# wifi_board.net
KiCad netlist of a schematic drawn in EAGLE
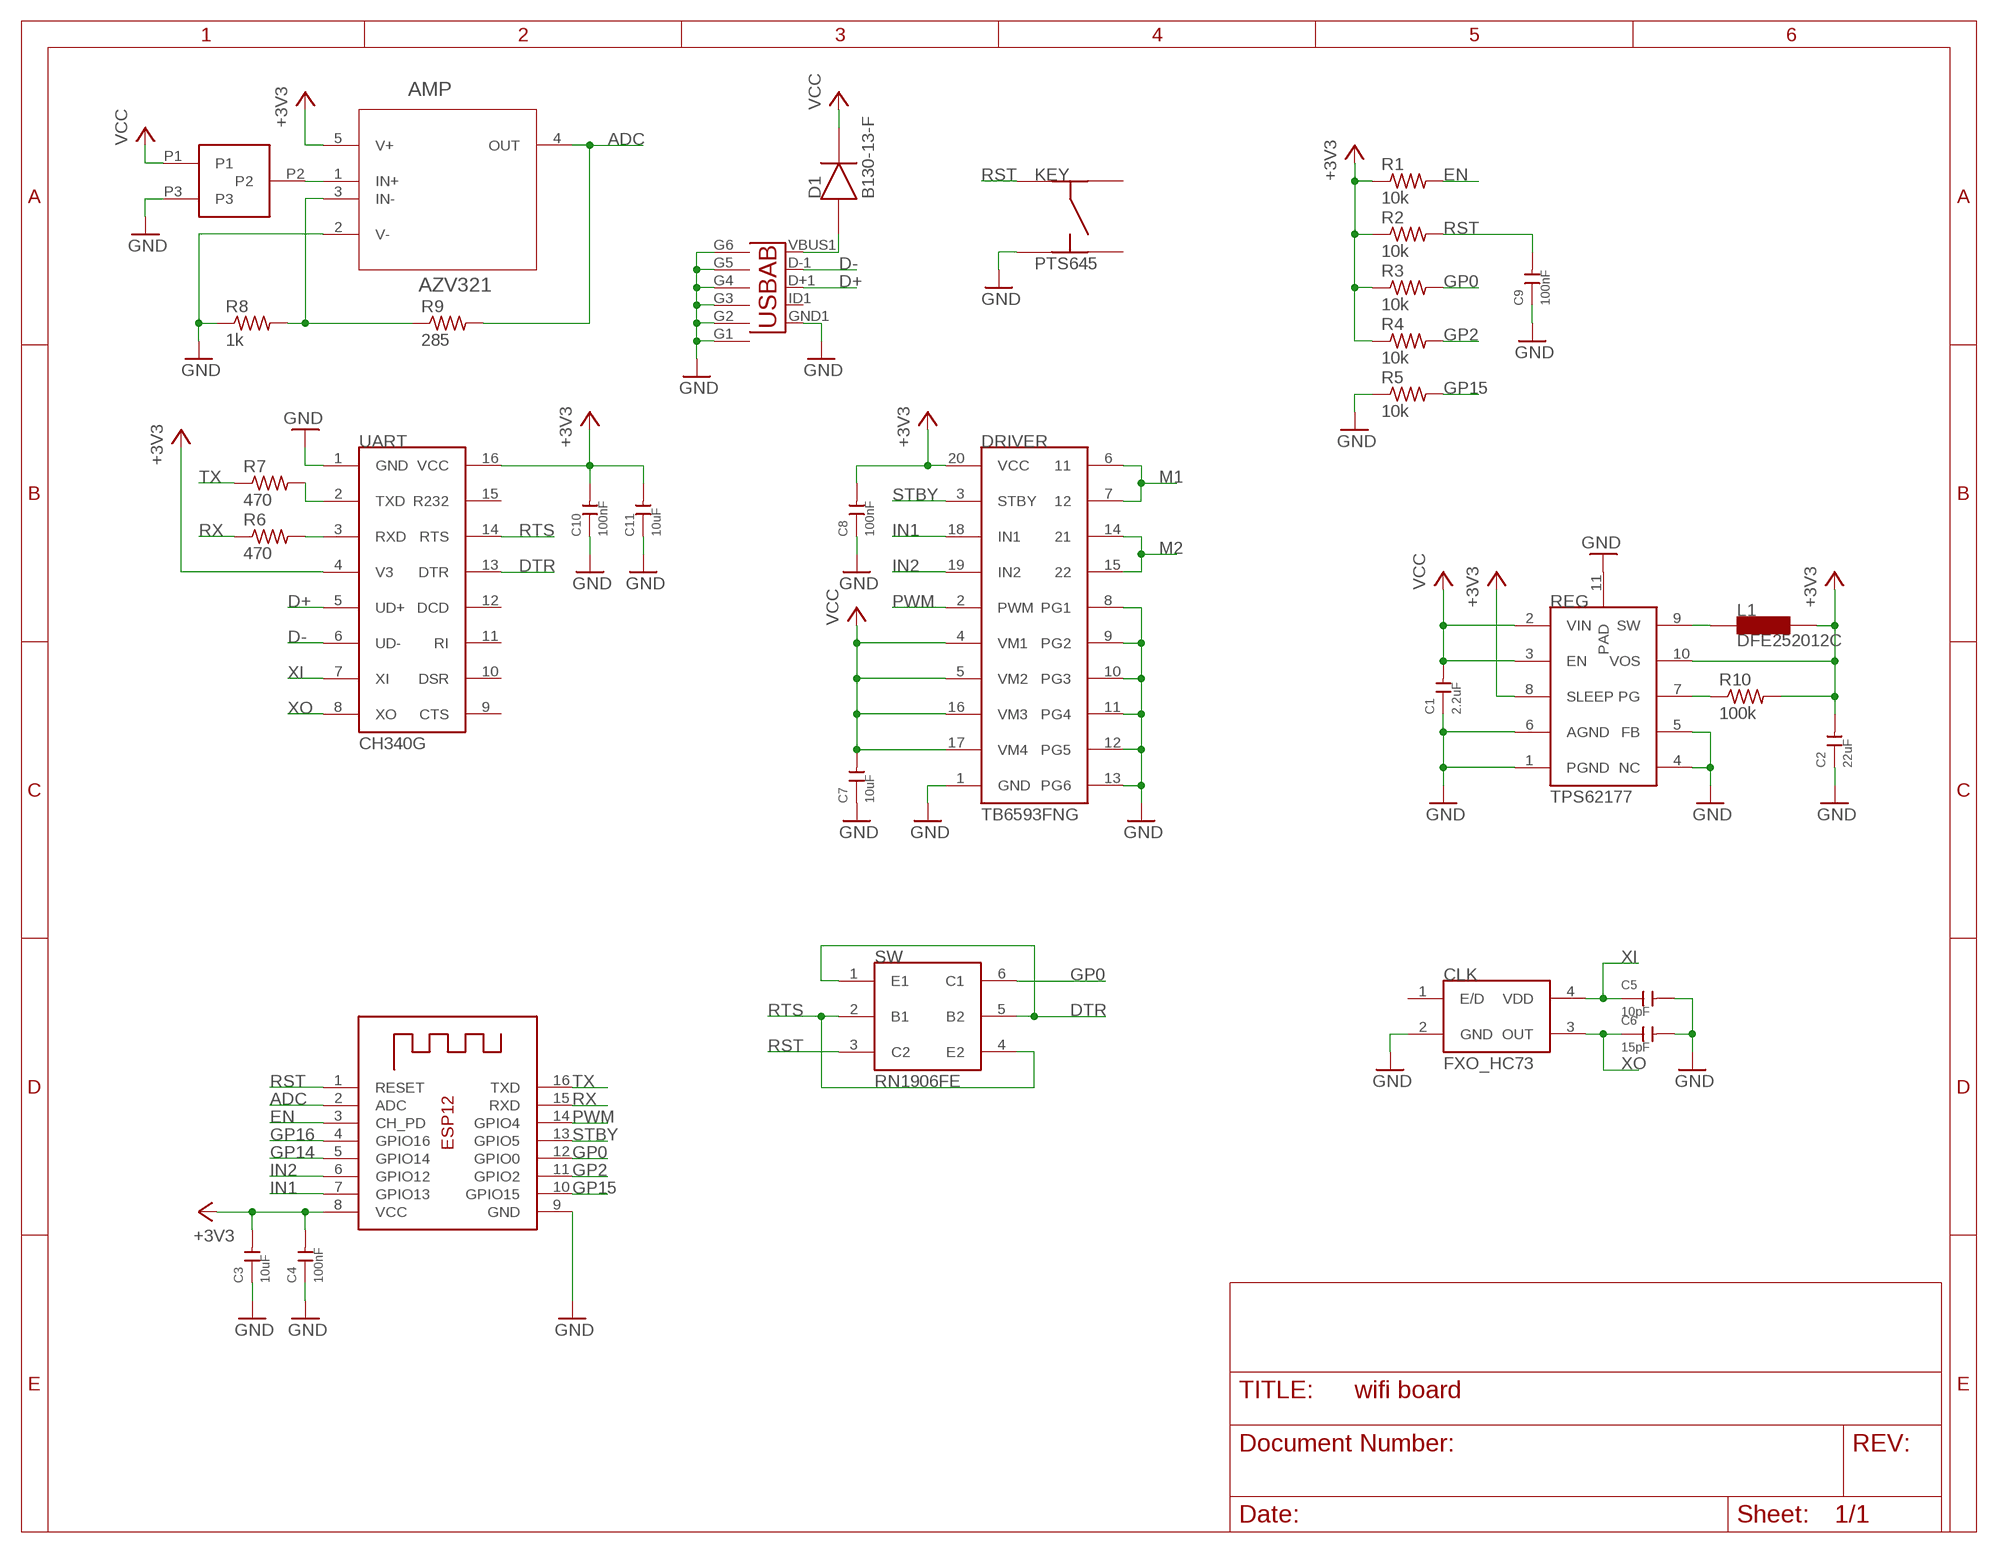
[diagram p0: schematic, sheet 1]

(export (version "E")
  (design (tool "Eeschema 10.0.6"))
  (components
    (comp (ref "AMP")
      (value "AZV321")
      (footprint "eagle-import:SOT65P210X110-5N")
      (fields (field (name "MPN") "LMV321SEG-7"))
      (libsource (lib "eagle-import") (part "LMV321SEG-7"))
    )
    (comp (ref "C1")
      (value "2.2uF")
      (footprint "eagle-import:C0603")
      (libsource (lib "eagle-import") (part "CERAMIC-0.5PF-50V-0.1PF-NPO(0603)"))
    )
    (comp (ref "C2")
      (value "22uF")
      (footprint "eagle-import:C0603")
      (libsource (lib "eagle-import") (part "CERAMIC-0.5PF-50V-0.1PF-NPO(0603)"))
    )
    (comp (ref "C3")
      (value "10uF")
      (footprint "eagle-import:C0603")
      (libsource (lib "eagle-import") (part "CERAMIC-0.5PF-50V-0.1PF-NPO(0603)"))
    )
    (comp (ref "C4")
      (value "100nF")
      (footprint "eagle-import:C0603")
      (libsource (lib "eagle-import") (part "CERAMIC-0.5PF-50V-0.1PF-NPO(0603)"))
    )
    (comp (ref "C5")
      (value "10pF")
      (footprint "eagle-import:C0603")
      (libsource (lib "eagle-import") (part "CERAMIC-0.5PF-50V-0.1PF-NPO(0603)"))
    )
    (comp (ref "C6")
      (value "15pF")
      (footprint "eagle-import:C0603")
      (libsource (lib "eagle-import") (part "CERAMIC-0.5PF-50V-0.1PF-NPO(0603)"))
    )
    (comp (ref "C7")
      (value "10uF")
      (footprint "eagle-import:C0603")
      (libsource (lib "eagle-import") (part "CERAMIC-0.5PF-50V-0.1PF-NPO(0603)"))
    )
    (comp (ref "C8")
      (value "100nF")
      (footprint "eagle-import:C0603")
      (libsource (lib "eagle-import") (part "CERAMIC-0.5PF-50V-0.1PF-NPO(0603)"))
    )
    (comp (ref "C9")
      (value "100nF")
      (footprint "eagle-import:C0603")
      (libsource (lib "eagle-import") (part "CERAMIC-1PF-50V-0.25PF-NPO(0603)"))
    )
    (comp (ref "C10")
      (value "100nF")
      (footprint "eagle-import:C0603")
      (libsource (lib "eagle-import") (part "CERAMIC-0.5PF-50V-0.1PF-NPO(0603)"))
    )
    (comp (ref "C11")
      (value "10uF")
      (footprint "eagle-import:C0603")
      (libsource (lib "eagle-import") (part "CERAMIC-0.5PF-50V-0.1PF-NPO(0603)"))
    )
    (comp (ref "CLK")
      (value "FXO_HC73")
      (footprint "eagle-import:4-SMD")
      (libsource (lib "eagle-import") (part "FXO_HC73"))
    )
    (comp (ref "CONN")
      (value "AVX_CONN")
      (footprint "eagle-import:AVX_CONN")
      (libsource (lib "eagle-import") (part "AVX_CONN"))
    )
    (comp (ref "D1")
      (value "B130-13-F")
      (footprint "eagle-import:SMA")
      (libsource (lib "eagle-import") (part "B130-13-F"))
    )
    (comp (ref "DRIVER")
      (value "TB6593FNG")
      (footprint "eagle-import:SSOP-20")
      (libsource (lib "eagle-import") (part "TB6593FNG"))
    )
    (comp (ref "ESP12")
      (value "ESP-12")
      (footprint "eagle-import:ESP-12")
      (libsource (lib "eagle-import") (part "ESP-12"))
    )
    (comp (ref "KEY")
      (value "PTS645")
      (footprint "eagle-import:BUTTON")
      (libsource (lib "eagle-import") (part "BUTTON"))
    )
    (comp (ref "L1")
      (value "DFE252012C")
      (footprint "eagle-import:1008")
      (libsource (lib "eagle-import") (part "DFE252012C"))
    )
    (comp (ref "R1")
      (value "10k")
      (footprint "eagle-import:R0603")
      (libsource (lib "eagle-import") (part "R-US_R0603"))
    )
    (comp (ref "R2")
      (value "10k")
      (footprint "eagle-import:R0603")
      (libsource (lib "eagle-import") (part "R-US_R0603"))
    )
    (comp (ref "R3")
      (value "10k")
      (footprint "eagle-import:R0603")
      (libsource (lib "eagle-import") (part "R-US_R0603"))
    )
    (comp (ref "R4")
      (value "10k")
      (footprint "eagle-import:R0603")
      (libsource (lib "eagle-import") (part "R-US_R0603"))
    )
    (comp (ref "R5")
      (value "10k")
      (footprint "eagle-import:R0603")
      (libsource (lib "eagle-import") (part "R-US_R0603"))
    )
    (comp (ref "R6")
      (value "470")
      (footprint "eagle-import:R0603")
      (libsource (lib "eagle-import") (part "R-US_R0603"))
    )
    (comp (ref "R7")
      (value "470")
      (footprint "eagle-import:R0603")
      (libsource (lib "eagle-import") (part "R-US_R0603"))
    )
    (comp (ref "R8")
      (value "1k")
      (footprint "eagle-import:R0603")
      (libsource (lib "eagle-import") (part "R-US_R0603"))
    )
    (comp (ref "R9")
      (value "285")
      (footprint "eagle-import:R0603")
      (libsource (lib "eagle-import") (part "R-US_R0603"))
    )
    (comp (ref "R10")
      (value "100k")
      (footprint "eagle-import:R0603")
      (libsource (lib "eagle-import") (part "R-US_R0603"))
    )
    (comp (ref "REG")
      (value "TPS62177")
      (footprint "eagle-import:WSON-10")
      (libsource (lib "eagle-import") (part "TPS62177"))
    )
    (comp (ref "SW")
      (value "RN1906FE")
      (footprint "eagle-import:SOT-563")
      (libsource (lib "eagle-import") (part "RN1906FE"))
    )
    (comp (ref "UART")
      (value "CH340G")
      (footprint "eagle-import:20-16")
      (libsource (lib "eagle-import") (part "CH340G"))
    )
    (comp (ref "USB")
      (value "USB\"\"")
      (footprint "eagle-import:USB-MICRO-SMD")
      (libsource (lib "eagle-import") (part "USB{dblquote}{dblquote}"))
    )
  )
  (nets
    (net (code "1") (name "+3V3") (class "Default")
      (node (ref "AMP") (pin "5") (pinfunction "V+_5") (pintype "power_in"))
      (node (ref "C10") (pin "2") (pinfunction "2_2") (pintype "passive"))
      (node (ref "C11") (pin "2") (pinfunction "2_2") (pintype "passive"))
      (node (ref "C2") (pin "2") (pinfunction "2_2") (pintype "passive"))
      (node (ref "C3") (pin "2") (pinfunction "2_2") (pintype "passive"))
      (node (ref "C4") (pin "2") (pinfunction "2_2") (pintype "passive"))
      (node (ref "C8") (pin "2") (pinfunction "2_2") (pintype "passive"))
      (node (ref "DRIVER") (pin "20") (pinfunction "VCC_20") (pintype "bidirectional"))
      (node (ref "ESP12") (pin "8") (pinfunction "VCC_8") (pintype "power_in"))
      (node (ref "L1") (pin "P$3") (pinfunction "P$2_P$3") (pintype "bidirectional"))
      (node (ref "R1") (pin "1") (pinfunction "1_1") (pintype "passive"))
      (node (ref "R10") (pin "2") (pinfunction "2_2") (pintype "passive"))
      (node (ref "R2") (pin "1") (pinfunction "1_1") (pintype "passive"))
      (node (ref "R3") (pin "1") (pinfunction "1_1") (pintype "passive"))
      (node (ref "R4") (pin "1") (pinfunction "1_1") (pintype "passive"))
      (node (ref "REG") (pin "10") (pinfunction "VOS_10") (pintype "bidirectional"))
      (node (ref "REG") (pin "8") (pinfunction "SLEEP_8") (pintype "bidirectional"))
      (node (ref "UART") (pin "16") (pinfunction "VCC_16") (pintype "bidirectional"))
      (node (ref "UART") (pin "4") (pinfunction "V3_4") (pintype "bidirectional"))
    )
    (net (code "2") (name "/ADC") (class "Default")
      (node (ref "AMP") (pin "4") (pinfunction "OUT_4") (pintype "output"))
      (node (ref "ESP12") (pin "2") (pinfunction "ADC_2") (pintype "passive"))
      (node (ref "R9") (pin "2") (pinfunction "2_2") (pintype "passive"))
    )
    (net (code "3") (name "/D+") (class "Default")
      (node (ref "UART") (pin "5") (pinfunction "UD+_5") (pintype "bidirectional"))
      (node (ref "USB") (pin "D+1") (pinfunction "D+_D+1") (pintype "bidirectional"))
    )
    (net (code "4") (name "/D-") (class "Default")
      (node (ref "UART") (pin "6") (pinfunction "UD-_6") (pintype "bidirectional"))
      (node (ref "USB") (pin "D-1") (pinfunction "D-_D-1") (pintype "bidirectional"))
    )
    (net (code "5") (name "/DTR") (class "Default")
      (node (ref "SW") (pin "1") (pinfunction "E1_1") (pintype "bidirectional"))
      (node (ref "SW") (pin "5") (pinfunction "B2_5") (pintype "bidirectional"))
      (node (ref "UART") (pin "13") (pinfunction "DTR_13") (pintype "bidirectional"))
    )
    (net (code "6") (name "/EN") (class "Default")
      (node (ref "ESP12") (pin "3") (pinfunction "CH_PD_3") (pintype "input"))
      (node (ref "R1") (pin "2") (pinfunction "2_2") (pintype "passive"))
    )
    (net (code "7") (name "/GP0") (class "Default")
      (node (ref "ESP12") (pin "12") (pinfunction "GPIO0_12") (pintype "bidirectional"))
      (node (ref "R3") (pin "2") (pinfunction "2_2") (pintype "passive"))
      (node (ref "SW") (pin "6") (pinfunction "C1_6") (pintype "bidirectional"))
    )
    (net (code "8") (name "/GP2") (class "Default")
      (node (ref "ESP12") (pin "11") (pinfunction "GPIO2_11") (pintype "bidirectional"))
      (node (ref "R4") (pin "2") (pinfunction "2_2") (pintype "passive"))
    )
    (net (code "9") (name "/GP14") (class "Default")
      (node (ref "ESP12") (pin "5") (pinfunction "GPIO14_5") (pintype "bidirectional"))
    )
    (net (code "10") (name "/GP15") (class "Default")
      (node (ref "ESP12") (pin "10") (pinfunction "GPIO15_10") (pintype "bidirectional"))
      (node (ref "R5") (pin "2") (pinfunction "2_2") (pintype "passive"))
    )
    (net (code "11") (name "/GP16") (class "Default")
      (node (ref "ESP12") (pin "4") (pinfunction "GPIO16_4") (pintype "bidirectional"))
    )
    (net (code "12") (name "/IN1") (class "Default")
      (node (ref "DRIVER") (pin "18") (pinfunction "IN1_18") (pintype "bidirectional"))
      (node (ref "ESP12") (pin "7") (pinfunction "GPIO13_7") (pintype "bidirectional"))
    )
    (net (code "13") (name "/IN2") (class "Default")
      (node (ref "DRIVER") (pin "19") (pinfunction "IN2_19") (pintype "bidirectional"))
      (node (ref "ESP12") (pin "6") (pinfunction "GPIO12_6") (pintype "bidirectional"))
    )
    (net (code "14") (name "/M1") (class "Default")
      (node (ref "DRIVER") (pin "6") (pinfunction "11_6") (pintype "bidirectional"))
      (node (ref "DRIVER") (pin "7") (pinfunction "12_7") (pintype "bidirectional"))
    )
    (net (code "15") (name "/M2") (class "Default")
      (node (ref "DRIVER") (pin "14") (pinfunction "21_14") (pintype "bidirectional"))
      (node (ref "DRIVER") (pin "15") (pinfunction "22_15") (pintype "bidirectional"))
    )
    (net (code "16") (name "/PWM") (class "Default")
      (node (ref "DRIVER") (pin "2") (pinfunction "PWM_2") (pintype "bidirectional"))
      (node (ref "ESP12") (pin "14") (pinfunction "GPIO4_14") (pintype "bidirectional"))
    )
    (net (code "17") (name "/RST") (class "Default")
      (node (ref "C9") (pin "2") (pinfunction "2_2") (pintype "passive"))
      (node (ref "ESP12") (pin "1") (pinfunction "RESET_1") (pintype "input"))
      (node (ref "KEY") (pin "1") (pinfunction "1_1") (pintype "bidirectional"))
      (node (ref "R2") (pin "2") (pinfunction "2_2") (pintype "passive"))
      (node (ref "SW") (pin "3") (pinfunction "C2_3") (pintype "bidirectional"))
    )
    (net (code "18") (name "/RTS") (class "Default")
      (node (ref "SW") (pin "2") (pinfunction "B1_2") (pintype "bidirectional"))
      (node (ref "SW") (pin "4") (pinfunction "E2_4") (pintype "bidirectional"))
      (node (ref "UART") (pin "14") (pinfunction "RTS_14") (pintype "bidirectional"))
    )
    (net (code "19") (name "/RX") (class "Default")
      (node (ref "ESP12") (pin "15") (pinfunction "RXD_15") (pintype "input"))
      (node (ref "R6") (pin "1") (pinfunction "1_1") (pintype "passive"))
    )
    (net (code "20") (name "/STBY") (class "Default")
      (node (ref "DRIVER") (pin "3") (pinfunction "STBY_3") (pintype "bidirectional"))
      (node (ref "ESP12") (pin "13") (pinfunction "GPIO5_13") (pintype "bidirectional"))
    )
    (net (code "21") (name "/TX") (class "Default")
      (node (ref "ESP12") (pin "16") (pinfunction "TXD_16") (pintype "output"))
      (node (ref "R7") (pin "1") (pinfunction "1_1") (pintype "passive"))
    )
    (net (code "22") (name "/XI") (class "Default")
      (node (ref "C5") (pin "1") (pinfunction "1_1") (pintype "passive"))
      (node (ref "CLK") (pin "4") (pinfunction "VDD_4") (pintype "bidirectional"))
      (node (ref "UART") (pin "7") (pinfunction "XI_7") (pintype "bidirectional"))
    )
    (net (code "23") (name "/XO") (class "Default")
      (node (ref "C6") (pin "1") (pinfunction "1_1") (pintype "passive"))
      (node (ref "CLK") (pin "3") (pinfunction "OUT_3") (pintype "bidirectional"))
      (node (ref "UART") (pin "8") (pinfunction "XO_8") (pintype "bidirectional"))
    )
    (net (code "24") (name "GND") (class "Default")
      (node (ref "AMP") (pin "2") (pinfunction "V-_2") (pintype "power_in"))
      (node (ref "C1") (pin "1") (pinfunction "1_1") (pintype "passive"))
      (node (ref "C10") (pin "1") (pinfunction "1_1") (pintype "passive"))
      (node (ref "C11") (pin "1") (pinfunction "1_1") (pintype "passive"))
      (node (ref "C2") (pin "1") (pinfunction "1_1") (pintype "passive"))
      (node (ref "C3") (pin "1") (pinfunction "1_1") (pintype "passive"))
      (node (ref "C4") (pin "1") (pinfunction "1_1") (pintype "passive"))
      (node (ref "C5") (pin "2") (pinfunction "2_2") (pintype "passive"))
      (node (ref "C6") (pin "2") (pinfunction "2_2") (pintype "passive"))
      (node (ref "C7") (pin "1") (pinfunction "1_1") (pintype "passive"))
      (node (ref "C8") (pin "1") (pinfunction "1_1") (pintype "passive"))
      (node (ref "C9") (pin "1") (pinfunction "1_1") (pintype "passive"))
      (node (ref "CLK") (pin "2") (pinfunction "GND_2") (pintype "bidirectional"))
      (node (ref "CONN") (pin "P3") (pinfunction "P3_P3") (pintype "bidirectional"))
      (node (ref "DRIVER") (pin "1") (pinfunction "GND_1") (pintype "bidirectional"))
      (node (ref "DRIVER") (pin "10") (pinfunction "PG3_10") (pintype "bidirectional"))
      (node (ref "DRIVER") (pin "11") (pinfunction "PG4_11") (pintype "bidirectional"))
      (node (ref "DRIVER") (pin "12") (pinfunction "PG5_12") (pintype "bidirectional"))
      (node (ref "DRIVER") (pin "13") (pinfunction "PG6_13") (pintype "bidirectional"))
      (node (ref "DRIVER") (pin "8") (pinfunction "PG1_8") (pintype "bidirectional"))
      (node (ref "DRIVER") (pin "9") (pinfunction "PG2_9") (pintype "bidirectional"))
      (node (ref "ESP12") (pin "9") (pinfunction "GND_9") (pintype "power_in"))
      (node (ref "KEY") (pin "3") (pinfunction "3_3") (pintype "bidirectional"))
      (node (ref "R5") (pin "1") (pinfunction "1_1") (pintype "passive"))
      (node (ref "R8") (pin "1") (pinfunction "1_1") (pintype "passive"))
      (node (ref "REG") (pin "1") (pinfunction "PGND_1") (pintype "bidirectional"))
      (node (ref "REG") (pin "11") (pinfunction "PAD_11") (pintype "bidirectional"))
      (node (ref "REG") (pin "4") (pinfunction "NC_4") (pintype "bidirectional"))
      (node (ref "REG") (pin "5") (pinfunction "FB_5") (pintype "bidirectional"))
      (node (ref "REG") (pin "6") (pinfunction "AGND_6") (pintype "bidirectional"))
      (node (ref "UART") (pin "1") (pinfunction "GND_1") (pintype "bidirectional"))
      (node (ref "USB") (pin "G1") (pinfunction "G1_G1") (pintype "bidirectional"))
      (node (ref "USB") (pin "G2") (pinfunction "G2_G2") (pintype "bidirectional"))
      (node (ref "USB") (pin "G3") (pinfunction "G3_G3") (pintype "bidirectional"))
      (node (ref "USB") (pin "G4") (pinfunction "G4_G4") (pintype "bidirectional"))
      (node (ref "USB") (pin "G5") (pinfunction "G5_G5") (pintype "bidirectional"))
      (node (ref "USB") (pin "G6") (pinfunction "G6_G6") (pintype "bidirectional"))
      (node (ref "USB") (pin "GND1") (pinfunction "GND_GND1") (pintype "bidirectional"))
    )
    (net (code "25") (name "Net-(AMP-IN+)") (class "Default")
      (node (ref "AMP") (pin "1") (pinfunction "IN+_1") (pintype "input"))
      (node (ref "CONN") (pin "P2") (pinfunction "P2_P2") (pintype "bidirectional"))
    )
    (net (code "26") (name "Net-(AMP-IN-)") (class "Default")
      (node (ref "AMP") (pin "3") (pinfunction "IN-_3") (pintype "input"))
      (node (ref "R8") (pin "2") (pinfunction "2_2") (pintype "passive"))
      (node (ref "R9") (pin "1") (pinfunction "1_1") (pintype "passive"))
    )
    (net (code "27") (name "Net-(L1-P$1)") (class "Default")
      (node (ref "L1") (pin "P$2") (pinfunction "P$1_P$2") (pintype "bidirectional"))
      (node (ref "REG") (pin "9") (pinfunction "SW_9") (pintype "bidirectional"))
    )
    (net (code "28") (name "Net-(REG-PG)") (class "Default")
      (node (ref "R10") (pin "1") (pinfunction "1_1") (pintype "passive"))
      (node (ref "REG") (pin "7") (pinfunction "PG_7") (pintype "bidirectional"))
    )
    (net (code "29") (name "Net-(UART-RXD)") (class "Default")
      (node (ref "R6") (pin "2") (pinfunction "2_2") (pintype "passive"))
      (node (ref "UART") (pin "3") (pinfunction "RXD_3") (pintype "bidirectional"))
    )
    (net (code "30") (name "Net-(UART-TXD)") (class "Default")
      (node (ref "R7") (pin "2") (pinfunction "2_2") (pintype "passive"))
      (node (ref "UART") (pin "2") (pinfunction "TXD_2") (pintype "bidirectional"))
    )
    (net (code "31") (name "Net-(USB-VBUS)") (class "Default")
      (node (ref "D1") (pin "AN") (pinfunction "AN_AN") (pintype "bidirectional"))
      (node (ref "USB") (pin "VBUS1") (pinfunction "VBUS_VBUS1") (pintype "bidirectional"))
    )
    (net (code "32") (name "VCC") (class "Default")
      (node (ref "C1") (pin "2") (pinfunction "2_2") (pintype "passive"))
      (node (ref "C7") (pin "2") (pinfunction "2_2") (pintype "passive"))
      (node (ref "CONN") (pin "P1") (pinfunction "P1_P1") (pintype "bidirectional"))
      (node (ref "D1") (pin "CATH") (pinfunction "CATH_CATH") (pintype "bidirectional"))
      (node (ref "DRIVER") (pin "16") (pinfunction "VM3_16") (pintype "bidirectional"))
      (node (ref "DRIVER") (pin "17") (pinfunction "VM4_17") (pintype "bidirectional"))
      (node (ref "DRIVER") (pin "4") (pinfunction "VM1_4") (pintype "bidirectional"))
      (node (ref "DRIVER") (pin "5") (pinfunction "VM2_5") (pintype "bidirectional"))
      (node (ref "REG") (pin "2") (pinfunction "VIN_2") (pintype "bidirectional"))
      (node (ref "REG") (pin "3") (pinfunction "EN_3") (pintype "bidirectional"))
    )
    (net (code "33") (name "unconnected-(CLK-E{slash}D-Pad1)") (class "Default")
      (node (ref "CLK") (pin "1") (pinfunction "E/D_1") (pintype "bidirectional"))
    )
    (net (code "34") (name "unconnected-(KEY-Pad2)") (class "Default")
      (node (ref "KEY") (pin "2") (pinfunction "2_2") (pintype "bidirectional"))
    )
    (net (code "35") (name "unconnected-(KEY-Pad4)") (class "Default")
      (node (ref "KEY") (pin "4") (pinfunction "4_4") (pintype "bidirectional"))
    )
    (net (code "36") (name "unconnected-(UART-CTS-Pad9)") (class "Default")
      (node (ref "UART") (pin "9") (pinfunction "CTS_9") (pintype "bidirectional"))
    )
    (net (code "37") (name "unconnected-(UART-DCD-Pad12)") (class "Default")
      (node (ref "UART") (pin "12") (pinfunction "DCD_12") (pintype "bidirectional"))
    )
    (net (code "38") (name "unconnected-(UART-DSR-Pad10)") (class "Default")
      (node (ref "UART") (pin "10") (pinfunction "DSR_10") (pintype "bidirectional"))
    )
    (net (code "39") (name "unconnected-(UART-R232-Pad15)") (class "Default")
      (node (ref "UART") (pin "15") (pinfunction "R232_15") (pintype "bidirectional"))
    )
    (net (code "40") (name "unconnected-(UART-RI-Pad11)") (class "Default")
      (node (ref "UART") (pin "11") (pinfunction "RI_11") (pintype "bidirectional"))
    )
    (net (code "41") (name "unconnected-(USB-USBID-PadID1)") (class "Default")
      (node (ref "USB") (pin "ID1") (pinfunction "USBID_ID1") (pintype "bidirectional"))
    )
  )
)
